# USB.net
KiCad netlist of a schematic drawn in Altium Designer
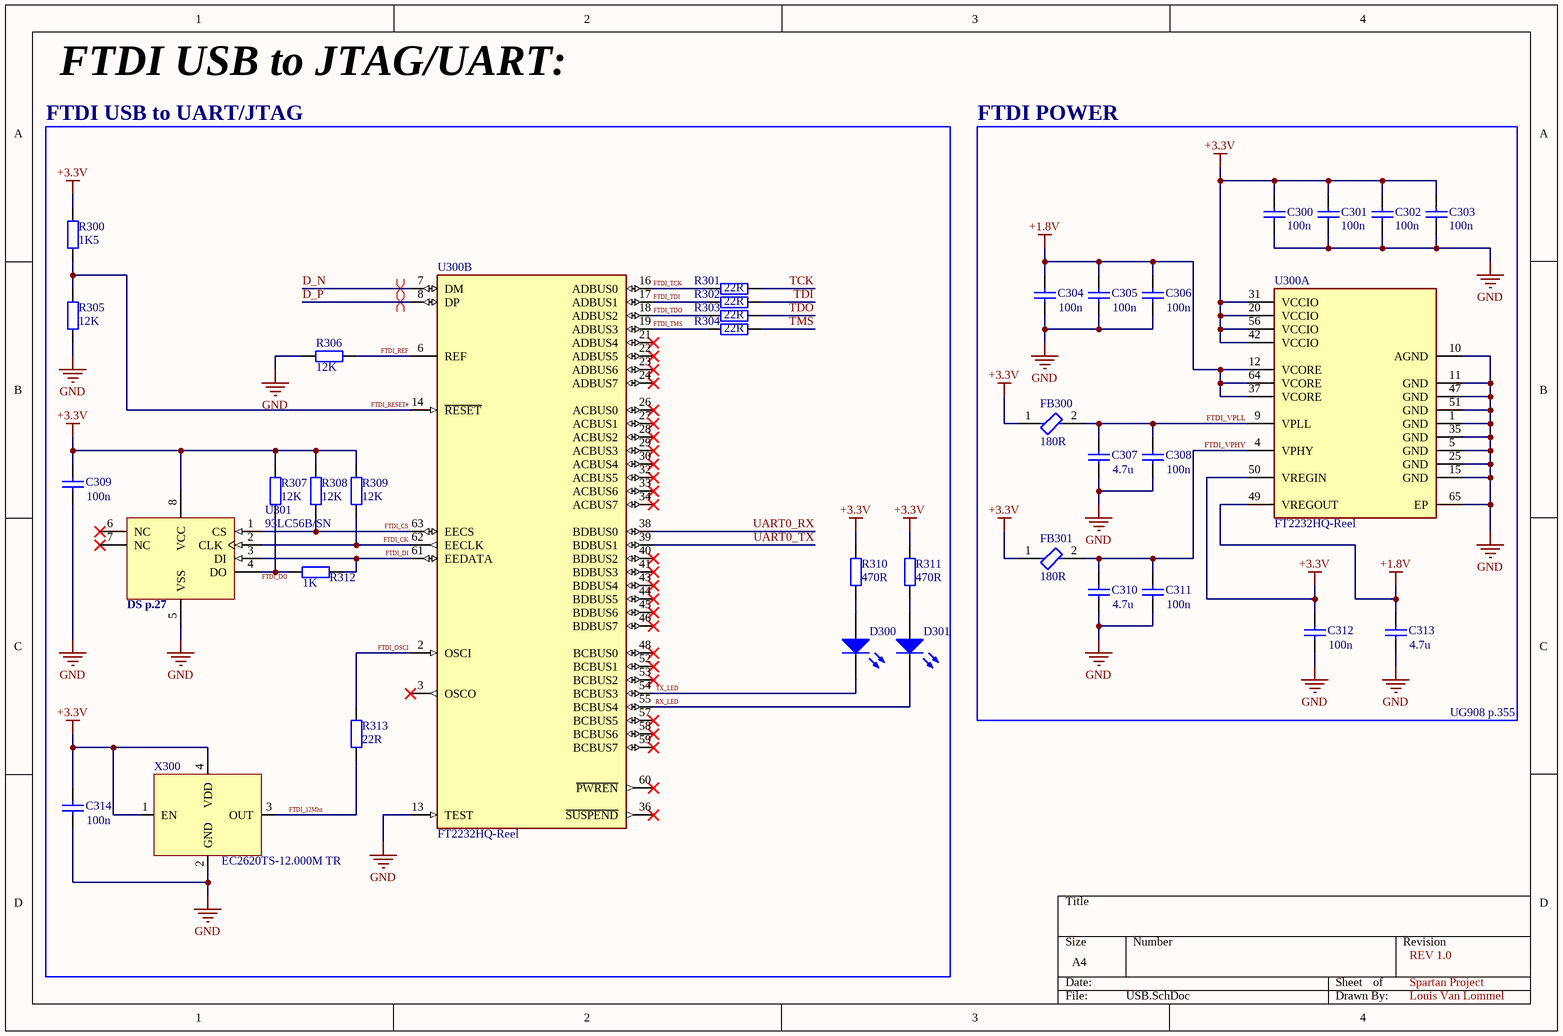
[diagram p0: USB.SchDoc]

(export (version "E")
  (design (tool "Eeschema 10.0.6"))
  (components
    (comp (ref "C300")
      (value "100n")
      (footprint "CAP_0603")
      (description "Capacitor")
      (fields (field (name "PUBLISHER") "Altium Limited"))
      (libsource (lib "Miscellaneous Devices") (part "Cap"))
    )
    (comp (ref "C301")
      (value "100n")
      (footprint "CAP_0603")
      (description "Capacitor")
      (fields (field (name "PUBLISHER") "Altium Limited"))
      (libsource (lib "Miscellaneous Devices") (part "Cap"))
    )
    (comp (ref "C302")
      (value "100n")
      (footprint "CAP_0603")
      (description "Capacitor")
      (fields (field (name "PUBLISHER") "Altium Limited"))
      (libsource (lib "Miscellaneous Devices") (part "Cap"))
    )
    (comp (ref "C303")
      (value "100n")
      (footprint "CAP_0603")
      (description "Capacitor")
      (fields (field (name "PUBLISHER") "Altium Limited"))
      (libsource (lib "Miscellaneous Devices") (part "Cap"))
    )
    (comp (ref "C304")
      (value "100n")
      (footprint "CAP_0603")
      (description "Capacitor")
      (fields (field (name "PUBLISHER") "Altium Limited"))
      (libsource (lib "Miscellaneous Devices") (part "Cap"))
    )
    (comp (ref "C305")
      (value "100n")
      (footprint "CAP_0603")
      (description "Capacitor")
      (fields (field (name "PUBLISHER") "Altium Limited"))
      (libsource (lib "Miscellaneous Devices") (part "Cap"))
    )
    (comp (ref "C306")
      (value "100n")
      (footprint "CAP_0603")
      (description "Capacitor")
      (fields (field (name "PUBLISHER") "Altium Limited"))
      (libsource (lib "Miscellaneous Devices") (part "Cap"))
    )
    (comp (ref "C307")
      (value "4.7u")
      (footprint "CAP_0603")
      (description "Capacitor")
      (fields (field (name "PUBLISHER") "Altium Limited"))
      (libsource (lib "Miscellaneous Devices") (part "Cap"))
    )
    (comp (ref "C308")
      (value "100n")
      (footprint "CAP_0603")
      (description "Capacitor")
      (fields (field (name "PUBLISHER") "Altium Limited"))
      (libsource (lib "Miscellaneous Devices") (part "Cap"))
    )
    (comp (ref "C309")
      (value "100n")
      (footprint "CAP_0603")
      (description "Capacitor")
      (fields (field (name "PUBLISHER") "Altium Limited"))
      (libsource (lib "Miscellaneous Devices") (part "Cap"))
    )
    (comp (ref "C310")
      (value "4.7u")
      (footprint "CAP_0603")
      (description "Capacitor")
      (fields (field (name "PUBLISHER") "Altium Limited"))
      (libsource (lib "Miscellaneous Devices") (part "Cap"))
    )
    (comp (ref "C311")
      (value "100n")
      (footprint "CAP_0603")
      (description "Capacitor")
      (fields (field (name "PUBLISHER") "Altium Limited"))
      (libsource (lib "Miscellaneous Devices") (part "Cap"))
    )
    (comp (ref "C312")
      (value "100n")
      (footprint "CAP_0603")
      (description "Capacitor")
      (fields (field (name "PUBLISHER") "Altium Limited"))
      (libsource (lib "Miscellaneous Devices") (part "Cap"))
    )
    (comp (ref "C313")
      (value "4.7u")
      (footprint "CAP_0603")
      (description "Capacitor")
      (fields (field (name "PUBLISHER") "Altium Limited"))
      (libsource (lib "Miscellaneous Devices") (part "Cap"))
    )
    (comp (ref "C314")
      (value "100n")
      (footprint "CAP_0603")
      (description "Capacitor")
      (fields (field (name "PUBLISHER") "Altium Limited"))
      (libsource (lib "Miscellaneous Devices") (part "Cap"))
    )
    (comp (ref "D300")
      (value "LED")
      (footprint "LED_0603")
      (description "Typical INFRARED GaAs LED")
      (fields (field (name "PUBLISHER") "Altium Limited"))
      (libsource (lib "Miscellaneous Devices") (part "LED0"))
    )
    (comp (ref "D301")
      (value "LED")
      (footprint "LED_0603")
      (description "Typical INFRARED GaAs LED")
      (fields (field (name "PUBLISHER") "Altium Limited"))
      (libsource (lib "Miscellaneous Devices") (part "LED0"))
    )
    (comp (ref "FB300")
      (value "180R")
      (footprint "CAP_0805")
      (description "Chip Ferrite Bead, 0402, 1000Ω @ 100MHz, 0.65Ω, 25%, 300mA")
      (fields (field (name "TOLERANCE") "25%"))
      (libsource (lib "Schematic_Symbols") (part "Ferrite Bead"))
    )
    (comp (ref "FB301")
      (value "180R")
      (footprint "CAP_0805")
      (description "Chip Ferrite Bead, 0402, 1000Ω @ 100MHz, 0.65Ω, 25%, 300mA")
      (fields (field (name "TOLERANCE") "25%"))
      (libsource (lib "Schematic_Symbols") (part "Ferrite Bead"))
    )
    (comp (ref "R300")
      (value "1K5")
      (footprint "RES_0603")
      (description "Resistor")
      (fields (field (name "PUBLISHER") "Altium Limited"))
      (libsource (lib "Miscellaneous Devices") (part "Res2"))
    )
    (comp (ref "R301")
      (value "22R")
      (footprint "RES_0603")
      (description "Resistor")
      (fields (field (name "Comment") "22") (field (name "PUBLISHER") "Altium Limited"))
      (libsource (lib "") (part "Res2_1"))
    )
    (comp (ref "R302")
      (value "22R")
      (footprint "RES_0603")
      (description "Resistor")
      (fields (field (name "Comment") "22") (field (name "PUBLISHER") "Altium Limited"))
      (libsource (lib "") (part "Res2_1"))
    )
    (comp (ref "R303")
      (value "22R")
      (footprint "RES_0603")
      (description "Resistor")
      (fields (field (name "Comment") "22") (field (name "PUBLISHER") "Altium Limited"))
      (libsource (lib "") (part "Res2_1"))
    )
    (comp (ref "R304")
      (value "22R")
      (footprint "RES_0603")
      (description "Resistor")
      (fields (field (name "Comment") "22") (field (name "PUBLISHER") "Altium Limited"))
      (libsource (lib "") (part "Res2_1"))
    )
    (comp (ref "R305")
      (value "12K")
      (footprint "RES_0603")
      (description "Resistor")
      (fields (field (name "PUBLISHER") "Altium Limited"))
      (libsource (lib "Miscellaneous Devices") (part "Res2"))
    )
    (comp (ref "R306")
      (value "12K")
      (footprint "RES_0603")
      (description "Resistor")
      (fields (field (name "PUBLISHER") "Altium Limited"))
      (libsource (lib "") (part "Res2_3"))
    )
    (comp (ref "R307")
      (value "12K")
      (footprint "RES_0603")
      (description "Resistor")
      (fields (field (name "PUBLISHER") "Altium Limited"))
      (libsource (lib "") (part "Res2_2"))
    )
    (comp (ref "R308")
      (value "12K")
      (footprint "RES_0603")
      (description "Resistor")
      (fields (field (name "PUBLISHER") "Altium Limited"))
      (libsource (lib "") (part "Res2_2"))
    )
    (comp (ref "R309")
      (value "12K")
      (footprint "RES_0603")
      (description "Resistor")
      (fields (field (name "PUBLISHER") "Altium Limited"))
      (libsource (lib "") (part "Res2_2"))
    )
    (comp (ref "R310")
      (value "470R")
      (footprint "RES_0603")
      (description "Resistor")
      (fields (field (name "Comment") "470") (field (name "PUBLISHER") "Altium Limited"))
      (libsource (lib "Miscellaneous Devices") (part "Res2"))
    )
    (comp (ref "R311")
      (value "470R")
      (footprint "RES_0603")
      (description "Resistor")
      (fields (field (name "Comment") "470") (field (name "PUBLISHER") "Altium Limited"))
      (libsource (lib "Miscellaneous Devices") (part "Res2"))
    )
    (comp (ref "R312")
      (value "1K")
      (footprint "RES_0603")
      (description "Resistor")
      (fields (field (name "PUBLISHER") "Altium Limited"))
      (libsource (lib "") (part "Res2_1"))
    )
    (comp (ref "R313")
      (value "22R")
      (footprint "RES_0603")
      (description "Resistor")
      (fields (field (name "Comment") "22") (field (name "PUBLISHER") "Altium Limited"))
      (libsource (lib "") (part "Res2_2"))
    )
    (comp (ref "U300")
      (value "FT2232HQ-Reel")
      (footprint "FP-FT2232HQ-Reel-MFG")
      (description "IC USB HS DUAL UART/FIFO 64-QFN")
      (fields
        (field (name "OCTOPART") "https://octopart.com/ft2232hq-reel-ftdi-19172126")
        (field (name "MANUFACTURER") "FTDI")
      )
      (libsource (lib "Altium Content Vault") (part "69ab9ac86b67af101dfdf5de5064102"))
    )
    (comp (ref "U301")
      (value "93LC56B/SN")
      (footprint "SOIC8")
      (description "2K, 128x16-bit, 2.5V Microwire Serial EEPROM, 8-Pin SOIC 150mil, Commercial Temperature")
      (libsource (lib "Schematic_Symbols") (part "MEM-SEEPROM-93AA46B-P-8"))
    )
    (comp (ref "X300")
      (value "EC2620TS-12.000M TR")
      (footprint "7x5mm Crystal")
      (description "12Mhz oscillator")
      (libsource (lib "Schematic_Symbols") (part "Oscillator"))
    )
  )
  (nets
    (net (code "1") (name "+1.8V") (class "Default")
      (node (ref "C304") (pin "2") (pinfunction "2_2") (pintype "passive"))
      (node (ref "C305") (pin "2") (pinfunction "2_2") (pintype "passive"))
      (node (ref "C306") (pin "2") (pinfunction "2_2") (pintype "passive"))
      (node (ref "C313") (pin "2") (pinfunction "2_2") (pintype "passive"))
      (node (ref "U300") (pin "12") (pinfunction "VCORE_12") (pintype "power_in"))
      (node (ref "U300") (pin "37") (pinfunction "VCORE_37") (pintype "power_in"))
      (node (ref "U300") (pin "49") (pinfunction "VREGOUT_49") (pintype "power_in"))
      (node (ref "U300") (pin "64") (pinfunction "VCORE_64") (pintype "power_in"))
    )
    (net (code "2") (name "+3.3V") (class "Default")
      (node (ref "C300") (pin "2") (pinfunction "2_2") (pintype "passive"))
      (node (ref "C301") (pin "2") (pinfunction "2_2") (pintype "passive"))
      (node (ref "C302") (pin "2") (pinfunction "2_2") (pintype "passive"))
      (node (ref "C303") (pin "2") (pinfunction "2_2") (pintype "passive"))
      (node (ref "C309") (pin "2") (pinfunction "2_2") (pintype "passive"))
      (node (ref "C312") (pin "2") (pinfunction "2_2") (pintype "passive"))
      (node (ref "C314") (pin "2") (pinfunction "2_2") (pintype "passive"))
      (node (ref "FB300") (pin "1") (pinfunction "1_1") (pintype "passive"))
      (node (ref "FB301") (pin "1") (pinfunction "1_1") (pintype "passive"))
      (node (ref "R300") (pin "2") (pinfunction "2_2") (pintype "passive"))
      (node (ref "R307") (pin "1") (pinfunction "1_1") (pintype "passive"))
      (node (ref "R308") (pin "1") (pinfunction "1_1") (pintype "passive"))
      (node (ref "R309") (pin "1") (pinfunction "1_1") (pintype "passive"))
      (node (ref "R310") (pin "2") (pinfunction "2_2") (pintype "passive"))
      (node (ref "R311") (pin "2") (pinfunction "2_2") (pintype "passive"))
      (node (ref "U300") (pin "20") (pinfunction "VCCIO_20") (pintype "power_in"))
      (node (ref "U300") (pin "31") (pinfunction "VCCIO_31") (pintype "power_in"))
      (node (ref "U300") (pin "42") (pinfunction "VCCIO_42") (pintype "power_in"))
      (node (ref "U300") (pin "50") (pinfunction "VREGIN_50") (pintype "power_in"))
      (node (ref "U300") (pin "56") (pinfunction "VCCIO_56") (pintype "power_in"))
      (node (ref "U301") (pin "8") (pinfunction "VCC_8") (pintype "power_in"))
      (node (ref "X300") (pin "1") (pinfunction "EN_1") (pintype "passive"))
      (node (ref "X300") (pin "4") (pinfunction "VDD_4") (pintype "passive"))
    )
    (net (code "3") (name "/D_N") (class "Default")
      (node (ref "U300") (pin "7") (pinfunction "DM_7") (pintype "bidirectional"))
    )
    (net (code "4") (name "/D_P") (class "Default")
      (node (ref "U300") (pin "8") (pinfunction "DP_8") (pintype "bidirectional"))
    )
    (net (code "5") (name "/FTDI_12Mhz") (class "Default")
      (node (ref "R313") (pin "2") (pinfunction "2_2") (pintype "passive"))
      (node (ref "X300") (pin "3") (pinfunction "OUT_3") (pintype "passive"))
    )
    (net (code "6") (name "/FTDI_CK") (class "Default")
      (node (ref "R309") (pin "2") (pinfunction "2_2") (pintype "passive"))
      (node (ref "U300") (pin "62") (pinfunction "EECLK_62") (pintype "output"))
      (node (ref "U301") (pin "2") (pinfunction "CLK_2") (pintype "input"))
    )
    (net (code "7") (name "/FTDI_CS") (class "Default")
      (node (ref "R308") (pin "2") (pinfunction "2_2") (pintype "passive"))
      (node (ref "U300") (pin "63") (pinfunction "EECS_63") (pintype "bidirectional"))
      (node (ref "U301") (pin "1") (pinfunction "CS_1") (pintype "input"))
    )
    (net (code "8") (name "/FTDI_DI") (class "Default")
      (node (ref "R312") (pin "1") (pinfunction "1_1") (pintype "passive"))
      (node (ref "U300") (pin "61") (pinfunction "EEDATA_61") (pintype "bidirectional"))
      (node (ref "U301") (pin "3") (pinfunction "DI_3") (pintype "input"))
    )
    (net (code "9") (name "/FTDI_DO") (class "Default")
      (node (ref "R307") (pin "2") (pinfunction "2_2") (pintype "passive"))
      (node (ref "R312") (pin "2") (pinfunction "2_2") (pintype "passive"))
      (node (ref "U301") (pin "4") (pinfunction "DO_4") (pintype "tri_state"))
    )
    (net (code "10") (name "/FTDI_OSCI") (class "Default")
      (node (ref "R313") (pin "1") (pinfunction "1_1") (pintype "passive"))
      (node (ref "U300") (pin "2") (pinfunction "OSCI_2") (pintype "input"))
    )
    (net (code "11") (name "/FTDI_REF") (class "Default")
      (node (ref "R306") (pin "2") (pinfunction "2_2") (pintype "passive"))
      (node (ref "U300") (pin "6") (pinfunction "REF_6") (pintype "passive"))
    )
    (net (code "12") (name "/FTDI_RESET#") (class "Default")
      (node (ref "R300") (pin "1") (pinfunction "1_1") (pintype "passive"))
      (node (ref "R305") (pin "2") (pinfunction "2_2") (pintype "passive"))
      (node (ref "U300") (pin "14") (pinfunction "~{RESET}_14") (pintype "input"))
    )
    (net (code "13") (name "/FTDI_TCK") (class "Default")
      (node (ref "R301") (pin "2") (pinfunction "2_2") (pintype "passive"))
      (node (ref "U300") (pin "16") (pinfunction "ADBUS0_16") (pintype "bidirectional"))
    )
    (net (code "14") (name "/FTDI_TDI") (class "Default")
      (node (ref "R302") (pin "2") (pinfunction "2_2") (pintype "passive"))
      (node (ref "U300") (pin "17") (pinfunction "ADBUS1_17") (pintype "bidirectional"))
    )
    (net (code "15") (name "/FTDI_TDO") (class "Default")
      (node (ref "R303") (pin "2") (pinfunction "2_2") (pintype "passive"))
      (node (ref "U300") (pin "18") (pinfunction "ADBUS2_18") (pintype "bidirectional"))
    )
    (net (code "16") (name "/FTDI_TMS") (class "Default")
      (node (ref "R304") (pin "2") (pinfunction "2_2") (pintype "passive"))
      (node (ref "U300") (pin "19") (pinfunction "ADBUS3_19") (pintype "bidirectional"))
    )
    (net (code "17") (name "/FTDI_VPHY") (class "Default")
      (node (ref "C310") (pin "2") (pinfunction "2_2") (pintype "passive"))
      (node (ref "C311") (pin "2") (pinfunction "2_2") (pintype "passive"))
      (node (ref "FB301") (pin "2") (pinfunction "2_2") (pintype "passive"))
      (node (ref "U300") (pin "4") (pinfunction "VPHY_4") (pintype "power_in"))
    )
    (net (code "18") (name "/FTDI_VPLL") (class "Default")
      (node (ref "C307") (pin "2") (pinfunction "2_2") (pintype "passive"))
      (node (ref "C308") (pin "2") (pinfunction "2_2") (pintype "passive"))
      (node (ref "FB300") (pin "2") (pinfunction "2_2") (pintype "passive"))
      (node (ref "U300") (pin "9") (pinfunction "VPLL_9") (pintype "power_in"))
    )
    (net (code "19") (name "/RX_LED") (class "Default")
      (node (ref "D301") (pin "2") (pinfunction "K_2") (pintype "passive"))
      (node (ref "U300") (pin "55") (pinfunction "BCBUS4_55") (pintype "bidirectional"))
    )
    (net (code "20") (name "/TCK") (class "Default")
      (node (ref "R301") (pin "1") (pinfunction "1_1") (pintype "passive"))
    )
    (net (code "21") (name "/TDI") (class "Default")
      (node (ref "R302") (pin "1") (pinfunction "1_1") (pintype "passive"))
    )
    (net (code "22") (name "/TDO") (class "Default")
      (node (ref "R303") (pin "1") (pinfunction "1_1") (pintype "passive"))
    )
    (net (code "23") (name "/TMS") (class "Default")
      (node (ref "R304") (pin "1") (pinfunction "1_1") (pintype "passive"))
    )
    (net (code "24") (name "/TX_LED") (class "Default")
      (node (ref "D300") (pin "2") (pinfunction "K_2") (pintype "passive"))
      (node (ref "U300") (pin "54") (pinfunction "BCBUS3_54") (pintype "bidirectional"))
    )
    (net (code "25") (name "/UART0_RX") (class "Default")
      (node (ref "U300") (pin "38") (pinfunction "BDBUS0_38") (pintype "bidirectional"))
    )
    (net (code "26") (name "/UART0_TX") (class "Default")
      (node (ref "U300") (pin "39") (pinfunction "BDBUS1_39") (pintype "bidirectional"))
    )
    (net (code "27") (name "GND") (class "Default")
      (node (ref "C300") (pin "1") (pinfunction "1_1") (pintype "passive"))
      (node (ref "C301") (pin "1") (pinfunction "1_1") (pintype "passive"))
      (node (ref "C302") (pin "1") (pinfunction "1_1") (pintype "passive"))
      (node (ref "C303") (pin "1") (pinfunction "1_1") (pintype "passive"))
      (node (ref "C304") (pin "1") (pinfunction "1_1") (pintype "passive"))
      (node (ref "C305") (pin "1") (pinfunction "1_1") (pintype "passive"))
      (node (ref "C306") (pin "1") (pinfunction "1_1") (pintype "passive"))
      (node (ref "C307") (pin "1") (pinfunction "1_1") (pintype "passive"))
      (node (ref "C308") (pin "1") (pinfunction "1_1") (pintype "passive"))
      (node (ref "C309") (pin "1") (pinfunction "1_1") (pintype "passive"))
      (node (ref "C310") (pin "1") (pinfunction "1_1") (pintype "passive"))
      (node (ref "C311") (pin "1") (pinfunction "1_1") (pintype "passive"))
      (node (ref "C312") (pin "1") (pinfunction "1_1") (pintype "passive"))
      (node (ref "C313") (pin "1") (pinfunction "1_1") (pintype "passive"))
      (node (ref "C314") (pin "1") (pinfunction "1_1") (pintype "passive"))
      (node (ref "R305") (pin "1") (pinfunction "1_1") (pintype "passive"))
      (node (ref "R306") (pin "1") (pinfunction "1_1") (pintype "passive"))
      (node (ref "U300") (pin "1") (pinfunction "GND_1") (pintype "power_in"))
      (node (ref "U300") (pin "10") (pinfunction "AGND_10") (pintype "power_in"))
      (node (ref "U300") (pin "11") (pinfunction "GND_11") (pintype "power_in"))
      (node (ref "U300") (pin "13") (pinfunction "TEST_13") (pintype "input"))
      (node (ref "U300") (pin "15") (pinfunction "GND_15") (pintype "power_in"))
      (node (ref "U300") (pin "25") (pinfunction "GND_25") (pintype "power_in"))
      (node (ref "U300") (pin "35") (pinfunction "GND_35") (pintype "power_in"))
      (node (ref "U300") (pin "47") (pinfunction "GND_47") (pintype "power_in"))
      (node (ref "U300") (pin "5") (pinfunction "GND_5") (pintype "power_in"))
      (node (ref "U300") (pin "51") (pinfunction "GND_51") (pintype "power_in"))
      (node (ref "U300") (pin "65") (pinfunction "EP_65") (pintype "passive"))
      (node (ref "U301") (pin "5") (pinfunction "VSS_5") (pintype "power_in"))
      (node (ref "X300") (pin "2") (pinfunction "GND_2") (pintype "passive"))
    )
    (net (code "28") (name "Net-(D300-A)") (class "Default")
      (node (ref "D300") (pin "1") (pinfunction "A_1") (pintype "passive"))
      (node (ref "R310") (pin "1") (pinfunction "1_1") (pintype "passive"))
    )
    (net (code "29") (name "Net-(D301-A)") (class "Default")
      (node (ref "D301") (pin "1") (pinfunction "A_1") (pintype "passive"))
      (node (ref "R311") (pin "1") (pinfunction "1_1") (pintype "passive"))
    )
    (net (code "30") (name "unconnected-(U300B-ACBUS0-Pad26)") (class "Default")
      (node (ref "U300") (pin "26") (pinfunction "ACBUS0_26") (pintype "bidirectional+no_connect"))
    )
    (net (code "31") (name "unconnected-(U300B-ACBUS1-Pad27)") (class "Default")
      (node (ref "U300") (pin "27") (pinfunction "ACBUS1_27") (pintype "bidirectional+no_connect"))
    )
    (net (code "32") (name "unconnected-(U300B-ACBUS2-Pad28)") (class "Default")
      (node (ref "U300") (pin "28") (pinfunction "ACBUS2_28") (pintype "bidirectional+no_connect"))
    )
    (net (code "33") (name "unconnected-(U300B-ACBUS3-Pad29)") (class "Default")
      (node (ref "U300") (pin "29") (pinfunction "ACBUS3_29") (pintype "bidirectional+no_connect"))
    )
    (net (code "34") (name "unconnected-(U300B-ACBUS4-Pad30)") (class "Default")
      (node (ref "U300") (pin "30") (pinfunction "ACBUS4_30") (pintype "bidirectional+no_connect"))
    )
    (net (code "35") (name "unconnected-(U300B-ACBUS5-Pad32)") (class "Default")
      (node (ref "U300") (pin "32") (pinfunction "ACBUS5_32") (pintype "bidirectional+no_connect"))
    )
    (net (code "36") (name "unconnected-(U300B-ACBUS6-Pad33)") (class "Default")
      (node (ref "U300") (pin "33") (pinfunction "ACBUS6_33") (pintype "bidirectional+no_connect"))
    )
    (net (code "37") (name "unconnected-(U300B-ACBUS7-Pad34)") (class "Default")
      (node (ref "U300") (pin "34") (pinfunction "ACBUS7_34") (pintype "bidirectional+no_connect"))
    )
    (net (code "38") (name "unconnected-(U300B-ADBUS4-Pad21)") (class "Default")
      (node (ref "U300") (pin "21") (pinfunction "ADBUS4_21") (pintype "bidirectional+no_connect"))
    )
    (net (code "39") (name "unconnected-(U300B-ADBUS5-Pad22)") (class "Default")
      (node (ref "U300") (pin "22") (pinfunction "ADBUS5_22") (pintype "bidirectional+no_connect"))
    )
    (net (code "40") (name "unconnected-(U300B-ADBUS6-Pad23)") (class "Default")
      (node (ref "U300") (pin "23") (pinfunction "ADBUS6_23") (pintype "bidirectional+no_connect"))
    )
    (net (code "41") (name "unconnected-(U300B-ADBUS7-Pad24)") (class "Default")
      (node (ref "U300") (pin "24") (pinfunction "ADBUS7_24") (pintype "bidirectional+no_connect"))
    )
    (net (code "42") (name "unconnected-(U300B-BCBUS0-Pad48)") (class "Default")
      (node (ref "U300") (pin "48") (pinfunction "BCBUS0_48") (pintype "bidirectional+no_connect"))
    )
    (net (code "43") (name "unconnected-(U300B-BCBUS1-Pad52)") (class "Default")
      (node (ref "U300") (pin "52") (pinfunction "BCBUS1_52") (pintype "bidirectional+no_connect"))
    )
    (net (code "44") (name "unconnected-(U300B-BCBUS2-Pad53)") (class "Default")
      (node (ref "U300") (pin "53") (pinfunction "BCBUS2_53") (pintype "bidirectional+no_connect"))
    )
    (net (code "45") (name "unconnected-(U300B-BCBUS5-Pad57)") (class "Default")
      (node (ref "U300") (pin "57") (pinfunction "BCBUS5_57") (pintype "bidirectional+no_connect"))
    )
    (net (code "46") (name "unconnected-(U300B-BCBUS6-Pad58)") (class "Default")
      (node (ref "U300") (pin "58") (pinfunction "BCBUS6_58") (pintype "bidirectional+no_connect"))
    )
    (net (code "47") (name "unconnected-(U300B-BCBUS7-Pad59)") (class "Default")
      (node (ref "U300") (pin "59") (pinfunction "BCBUS7_59") (pintype "bidirectional+no_connect"))
    )
    (net (code "48") (name "unconnected-(U300B-BDBUS2-Pad40)") (class "Default")
      (node (ref "U300") (pin "40") (pinfunction "BDBUS2_40") (pintype "bidirectional+no_connect"))
    )
    (net (code "49") (name "unconnected-(U300B-BDBUS3-Pad41)") (class "Default")
      (node (ref "U300") (pin "41") (pinfunction "BDBUS3_41") (pintype "bidirectional+no_connect"))
    )
    (net (code "50") (name "unconnected-(U300B-BDBUS4-Pad43)") (class "Default")
      (node (ref "U300") (pin "43") (pinfunction "BDBUS4_43") (pintype "bidirectional+no_connect"))
    )
    (net (code "51") (name "unconnected-(U300B-BDBUS5-Pad44)") (class "Default")
      (node (ref "U300") (pin "44") (pinfunction "BDBUS5_44") (pintype "bidirectional+no_connect"))
    )
    (net (code "52") (name "unconnected-(U300B-BDBUS6-Pad45)") (class "Default")
      (node (ref "U300") (pin "45") (pinfunction "BDBUS6_45") (pintype "bidirectional+no_connect"))
    )
    (net (code "53") (name "unconnected-(U300B-BDBUS7-Pad46)") (class "Default")
      (node (ref "U300") (pin "46") (pinfunction "BDBUS7_46") (pintype "bidirectional+no_connect"))
    )
    (net (code "54") (name "unconnected-(U300B-OSCO-Pad3)") (class "Default")
      (node (ref "U300") (pin "3") (pinfunction "OSCO_3") (pintype "output+no_connect"))
    )
    (net (code "55") (name "unconnected-(U300B-~{PWREN}-Pad60)") (class "Default")
      (node (ref "U300") (pin "60") (pinfunction "~{PWREN}_60") (pintype "output+no_connect"))
    )
    (net (code "56") (name "unconnected-(U300B-~{SUSPEND}-Pad36)") (class "Default")
      (node (ref "U300") (pin "36") (pinfunction "~{SUSPEND}_36") (pintype "output+no_connect"))
    )
    (net (code "57") (name "unconnected-(U301-NC-Pad6)") (class "Default")
      (node (ref "U301") (pin "6") (pinfunction "NC_6") (pintype "passive+no_connect"))
    )
    (net (code "58") (name "unconnected-(U301-NC-Pad7)") (class "Default")
      (node (ref "U301") (pin "7") (pinfunction "NC_7") (pintype "passive+no_connect"))
    )
  )
)
